# 08_MCU_POWER.net
KiCad netlist of a schematic drawn in Altium Designer
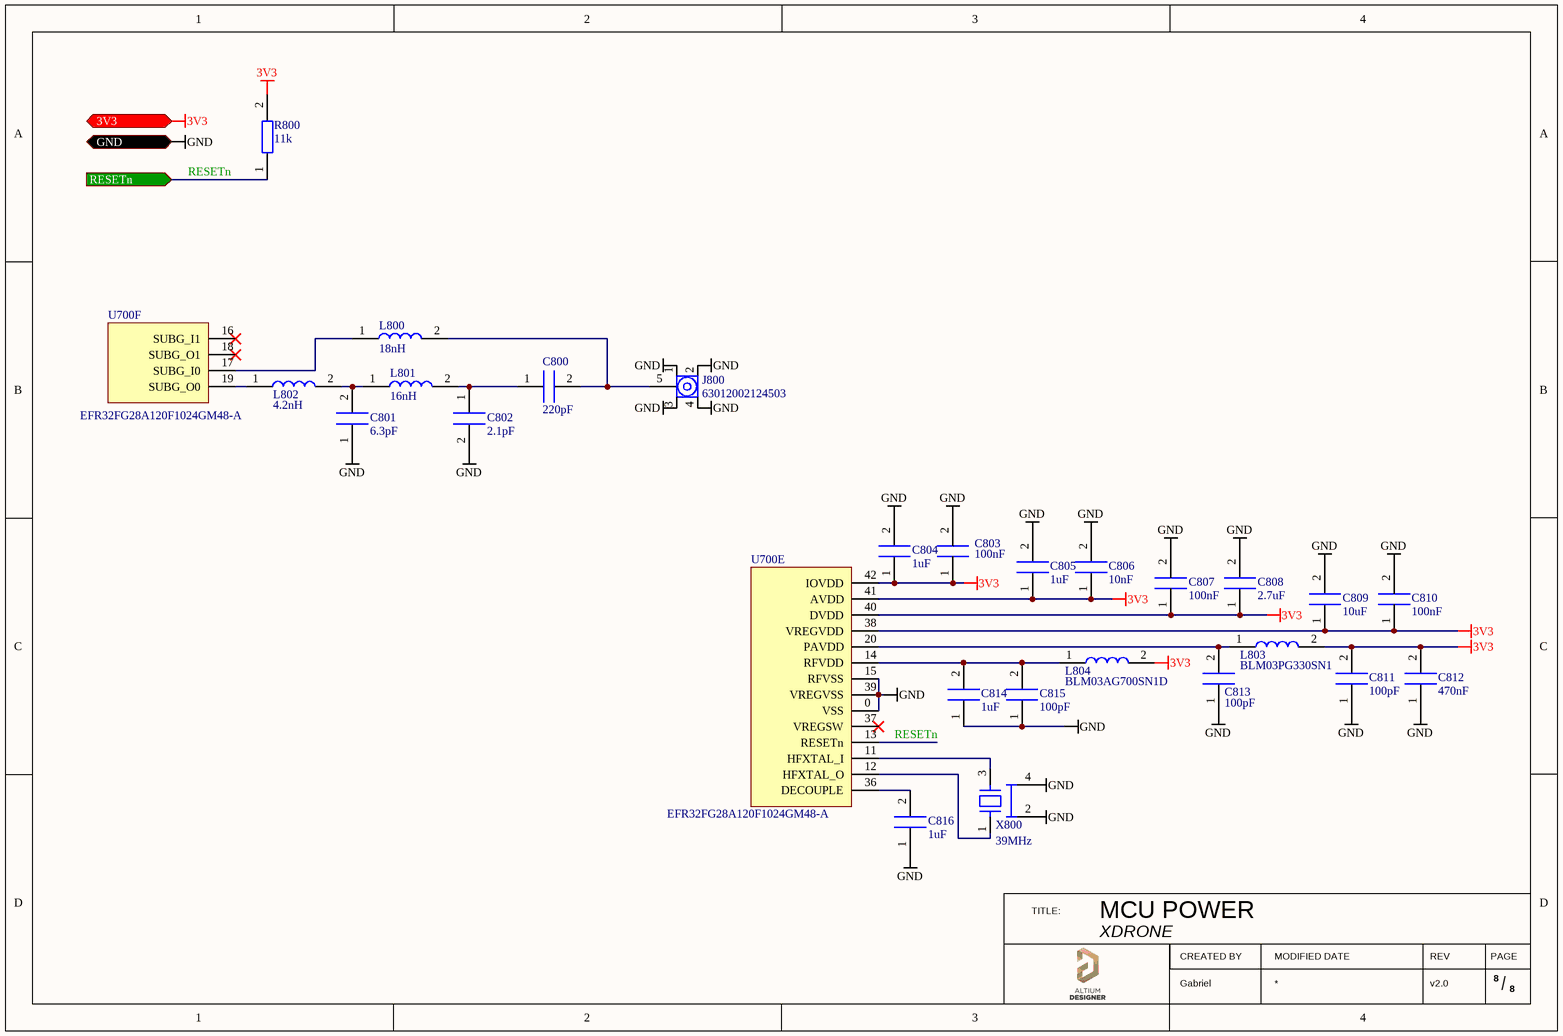
[diagram p0: 08_MCU_POWER.SchDoc]

(export (version "E")
  (design (tool "Eeschema 10.0.6"))
  (components
    (comp (ref "C800")
      (value "220pF")
      (footprint "CAP_0805")
      (description "CAP 220pF 5% 50V 0805 C0G,NP0")
      (fields (field (name "TOLERANCE") "5%") (field (name "MANUFACTURER") "JOHANSON TECHLONOGY"))
      (libsource (lib "Capacitors") (part "220pF_5%_50V_0805_C0G,NP0_QSCT251Q221J1GV001E"))
    )
    (comp (ref "C801")
      (value "6.3pF")
      (footprint "CAP_0402")
      (description "CAPACITOR 6.3pF 1.5% 50V 0402 CBR04C639B5GAC")
      (fields (field (name "TOLERANCE") "1.5%") (field (name "MANUFACTURER") "KEMET"))
      (libsource (lib "Capacitors") (part "6.3pF_1.5%_50V_0402_CBR04C639B5GAC"))
    )
    (comp (ref "C802")
      (value "2.1pF")
      (footprint "CAP_0402")
      (description "CAPACITOR 2.1pF 5% 50V 0402 GJM1555C1H2R1BB01D")
      (fields (field (name "TOLERANCE") "5%") (field (name "MANUFACTURER") "MURATA"))
      (libsource (lib "Capacitors") (part "2.1pF_5%_50V_0402_GJM1555C1H2R1BB01D"))
    )
    (comp (ref "C803")
      (value "100nF")
      (footprint "CAP_0402")
      (description "CAPACITOR 100nF 10% X7R 0402")
      (fields (field (name "TOLERANCE") "10%") (field (name "MANUFACTURER") "MURATA"))
      (libsource (lib "Capacitors") (part "100nF_10%_16V_0402_GRM155R71C104KA88J"))
    )
    (comp (ref "C804")
      (value "1uF")
      (footprint "CAP_0402")
      (description "CAPACITOR 1uF 10% X5R 0402")
      (fields (field (name "TOLERANCE") "10%") (field (name "MANUFACTURER") "MURATA"))
      (libsource (lib "Capacitors") (part "1uF_10%_35V_0402_GRM155R6YA105KE11J"))
    )
    (comp (ref "C805")
      (value "1uF")
      (footprint "CAP_0402")
      (description "CAPACITOR 1uF 10% X5R 0402")
      (fields (field (name "TOLERANCE") "10%") (field (name "MANUFACTURER") "MURATA"))
      (libsource (lib "Capacitors") (part "1uF_10%_35V_0402_GRM155R6YA105KE11J"))
    )
    (comp (ref "C806")
      (value "10nF")
      (footprint "CAP_0402")
      (description "CAPACITOR 10nF 10% 6.3V 0402 CC0402KRX7R5BB103")
      (fields (field (name "TOLERANCE") "10%") (field (name "MANUFACTURER") "YAGEO"))
      (libsource (lib "Capacitors") (part "10nF_10%_6.3V_0402_CC0402KRX7R5BB103"))
    )
    (comp (ref "C807")
      (value "100nF")
      (footprint "CAP_0402")
      (description "CAPACITOR 100nF 10% X7R 0402")
      (fields (field (name "TOLERANCE") "10%") (field (name "MANUFACTURER") "MURATA"))
      (libsource (lib "Capacitors") (part "100nF_10%_16V_0402_GRM155R71C104KA88J"))
    )
    (comp (ref "C808")
      (value "2.7uF")
      (footprint "CAP_0805")
      (description "CAP 2.7uF 10% 10V 0805 X5R C0805C275K8PAC7800")
      (fields (field (name "TOLERANCE") "10%") (field (name "MANUFACTURER") "KEMET"))
      (libsource (lib "Capacitors") (part "2.7uF_10%_10V_0805_X5R_C0805C275K8PAC7800"))
    )
    (comp (ref "C809")
      (value "10uF")
      (footprint "CAP_0402")
      (description "CAPACITOR 10uF 20% 6.3V 0402 GRM155R60J106ME05D")
      (fields (field (name "TOLERANCE") "20%") (field (name "MANUFACTURER") "MURATA"))
      (libsource (lib "Capacitors") (part "10uF 20% 6.3V 0402 GRM155R60J106ME05D"))
    )
    (comp (ref "C810")
      (value "100nF")
      (footprint "CAP_0402")
      (description "CAPACITOR 100nF 10% X7R 0402")
      (fields (field (name "TOLERANCE") "10%") (field (name "MANUFACTURER") "MURATA"))
      (libsource (lib "Capacitors") (part "100nF_10%_16V_0402_GRM155R71C104KA88J"))
    )
    (comp (ref "C811")
      (value "100pF")
      (footprint "CAP_0402")
      (description "CAPACITOR 100pF 5% 50V 0402 CC0402JRNPO9BN101")
      (fields (field (name "TOLERANCE") "5%") (field (name "MANUFACTURER") "YAGEO"))
      (libsource (lib "Capacitors") (part "100pF_5%_50V_0402_CC0402JRNPO9BN101"))
    )
    (comp (ref "C812")
      (value "470nF")
      (footprint "CAP_0402")
      (description "CAPACITOR 470nF 10% 6.3V 0402 GRM155C80J474KE19D")
      (fields (field (name "TOLERANCE") "10%") (field (name "MANUFACTURER") "MURATA"))
      (libsource (lib "Capacitors") (part "470nF_10%_6.3V_0402_GRM155C80J474KE19D"))
    )
    (comp (ref "C813")
      (value "100pF")
      (footprint "CAP_0402")
      (description "CAPACITOR 100pF 5% 50V 0402 CC0402JRNPO9BN101")
      (fields (field (name "TOLERANCE") "5%") (field (name "MANUFACTURER") "YAGEO"))
      (libsource (lib "Capacitors") (part "100pF_5%_50V_0402_CC0402JRNPO9BN101"))
    )
    (comp (ref "C814")
      (value "1uF")
      (footprint "CAP_0402")
      (description "CAPACITOR 1uF 10% X5R 0402")
      (fields (field (name "TOLERANCE") "10%") (field (name "MANUFACTURER") "MURATA"))
      (libsource (lib "Capacitors") (part "1uF_10%_35V_0402_GRM155R6YA105KE11J"))
    )
    (comp (ref "C815")
      (value "100pF")
      (footprint "CAP_0402")
      (description "CAPACITOR 100pF 5% 50V 0402 CC0402JRNPO9BN101")
      (fields (field (name "TOLERANCE") "5%") (field (name "MANUFACTURER") "YAGEO"))
      (libsource (lib "Capacitors") (part "100pF_5%_50V_0402_CC0402JRNPO9BN101"))
    )
    (comp (ref "C816")
      (value "1uF")
      (footprint "CAP_0402")
      (description "CAPACITOR 1uF 10% X5R 0402")
      (fields (field (name "TOLERANCE") "10%") (field (name "MANUFACTURER") "MURATA"))
      (libsource (lib "Capacitors") (part "1uF_10%_35V_0402_GRM155R6YA105KE11J"))
    )
    (comp (ref "J800")
      (value "RF_63012002124503")
      (footprint "RF_63012002124503")
      (description "RF Connector 63012002124503")
      (fields (field (name "MANUFACTURER") "WE") (field (name "MANUFACTURER REFERENCE") "63012002124503"))
      (libsource (lib "Connectors") (part "RF_63012002124503"))
    )
    (comp (ref "L800")
      (value "18nH")
      (footprint "RF_IND_0402")
      (description "INDUCTOR 18nH 2% 400mA LQG15HS18NG02D")
      (fields (field (name "TOLERANCE") "2%") (field (name "MANUFACTURER") "MURATA"))
      (libsource (lib "Inductors") (part "18nH_2%_400mA_LQG15HS18NG02D"))
    )
    (comp (ref "L801")
      (value "16nH")
      (footprint "RF_IND_0402")
      (description "INDUCTOR 16nH 3% 400mA MLG1005S16NHT000")
      (fields (field (name "TOLERANCE") "3%") (field (name "MANUFACTURER") "TDK"))
      (libsource (lib "Inductors") (part "16nH_3%_400mA_MLG1005S16NHT000"))
    )
    (comp (ref "L802")
      (value "4.2nH")
      (footprint "RF_IND_0402")
      (description "INDUCTOR 4.2nH 5% 1.8A LQW15AN4N2C8ZD")
      (fields (field (name "TOLERANCE") "5%") (field (name "MANUFACTURER") "MURATA"))
      (libsource (lib "Inductors") (part "4.2nH_5%_1.8A_LQW15AN4N2C8ZD"))
    )
    (comp (ref "L803")
      (value "52nH_25%_750mA_BLM03PG330SN1")
      (footprint "IND_0201")
      (description "INDUCTOR 52uH 25% 750mA BLM03PG330SN1")
      (fields
        (field (name "TOLERANCE") "25%")
        (field (name "MANUFACTURER") "MURATA")
        (field (name "MANUFACTURER REFERENCE") "BLM03PG330SN1")
      )
      (libsource (lib "Inductors") (part "52nH_25%_750mA_BLM03PG330SN1"))
    )
    (comp (ref "L804")
      (value "110nH_50%_200mA_BLM03AG700SN1D")
      (footprint "IND_0201")
      (description "INDUCTOR 110nH 50% 200mA BLM03AG700SN1D")
      (fields
        (field (name "TOLERANCE") "50%")
        (field (name "MANUFACTURER") "MURATA")
        (field (name "MANUFACTURER REFERENCE") "BLM03AG700SN1D")
      )
      (libsource (lib "Inductors") (part "110nH 50% 200mA BLM03AG700SN1D"))
    )
    (comp (ref "R800")
      (value "11k")
      (footprint "RES_0402")
      (description "RESISTOR 11k 5% 0402 ERJ-2GEJ113X")
      (fields (field (name "TOLERANCE") "5%") (field (name "MANUFACTURER") "PANASONIC"))
      (libsource (lib "Resistors") (part "RES_11k_5%_0402_ERJ-2GEJ113X"))
    )
    (comp (ref "U700")
      (value "MCU_1MB_256kB_EFR32FG28A120F1024GM48-A")
      (footprint "QFN48")
      (description "MCU 1MB 256kB EFR32FG28A120F1024GM48-A")
      (fields
        (field (name "MANUFACTURER") "SILICON LABS")
        (field (name "MANUFACTURER REFERENCE") "EFR32FG28A120F1024GM48-A")
      )
      (libsource (lib "Semiconductor") (part "MCU_1MB_256kB_EFR32FG28A120F1024GM48-A"))
    )
    (comp (ref "X800")
      (value "QUARTZ_39MHz_10ppm_ECS-390-10-37B-CKM-TR")
      (footprint "4-SMD")
      (description "QUARTZ 39MHz 10ppm ECS-390-10-37B-CKM-TR")
      (fields
        (field (name "MANUFACTURER") "ECS")
        (field (name "TOLERANCE") "10 ppm")
        (field (name "FREQUENCY") "39MHz")
      )
      (libsource (lib "Oscillators") (part "QUARTZ_39MHz_10ppm_ECS-390-10-37B-CKM-TR"))
    )
  )
  (nets
    (net (code "1") (name "/RESETn") (class "Default")
      (node (ref "R800") (pin "1") (pinfunction "1_1") (pintype "passive"))
      (node (ref "U700") (pin "13") (pinfunction "RESETn_13") (pintype "passive"))
    )
    (net (code "2") (name "3V3") (class "Default")
      (node (ref "C803") (pin "1") (pinfunction "1_1") (pintype "passive"))
      (node (ref "C804") (pin "1") (pinfunction "1_1") (pintype "passive"))
      (node (ref "C805") (pin "1") (pinfunction "1_1") (pintype "passive"))
      (node (ref "C806") (pin "1") (pinfunction "1_1") (pintype "passive"))
      (node (ref "C807") (pin "1") (pinfunction "1_1") (pintype "passive"))
      (node (ref "C808") (pin "1") (pinfunction "1_1") (pintype "passive"))
      (node (ref "C809") (pin "1") (pinfunction "1_1") (pintype "passive"))
      (node (ref "C810") (pin "1") (pinfunction "1_1") (pintype "passive"))
      (node (ref "C811") (pin "2") (pinfunction "2_2") (pintype "passive"))
      (node (ref "C812") (pin "2") (pinfunction "2_2") (pintype "passive"))
      (node (ref "L803") (pin "2") (pinfunction "2_2") (pintype "passive"))
      (node (ref "L804") (pin "2") (pinfunction "2_2") (pintype "passive"))
      (node (ref "R800") (pin "2") (pinfunction "2_2") (pintype "passive"))
      (node (ref "U700") (pin "38") (pinfunction "VREGVDD_38") (pintype "passive"))
      (node (ref "U700") (pin "40") (pinfunction "DVDD_40") (pintype "passive"))
      (node (ref "U700") (pin "41") (pinfunction "AVDD_41") (pintype "passive"))
      (node (ref "U700") (pin "42") (pinfunction "IOVDD_42") (pintype "passive"))
    )
    (net (code "3") (name "GND") (class "Default")
      (node (ref "C801") (pin "1") (pinfunction "1_1") (pintype "passive"))
      (node (ref "C802") (pin "2") (pinfunction "2_2") (pintype "passive"))
      (node (ref "C803") (pin "2") (pinfunction "2_2") (pintype "passive"))
      (node (ref "C804") (pin "2") (pinfunction "2_2") (pintype "passive"))
      (node (ref "C805") (pin "2") (pinfunction "2_2") (pintype "passive"))
      (node (ref "C806") (pin "2") (pinfunction "2_2") (pintype "passive"))
      (node (ref "C807") (pin "2") (pinfunction "2_2") (pintype "passive"))
      (node (ref "C808") (pin "2") (pinfunction "2_2") (pintype "passive"))
      (node (ref "C809") (pin "2") (pinfunction "2_2") (pintype "passive"))
      (node (ref "C810") (pin "2") (pinfunction "2_2") (pintype "passive"))
      (node (ref "C811") (pin "1") (pinfunction "1_1") (pintype "passive"))
      (node (ref "C812") (pin "1") (pinfunction "1_1") (pintype "passive"))
      (node (ref "C813") (pin "1") (pinfunction "1_1") (pintype "passive"))
      (node (ref "C814") (pin "1") (pinfunction "1_1") (pintype "passive"))
      (node (ref "C815") (pin "1") (pinfunction "1_1") (pintype "passive"))
      (node (ref "C816") (pin "1") (pinfunction "1_1") (pintype "passive"))
      (node (ref "J800") (pin "1") (pinfunction "1_1") (pintype "passive"))
      (node (ref "J800") (pin "2") (pinfunction "2_2") (pintype "passive"))
      (node (ref "J800") (pin "3") (pinfunction "3_3") (pintype "passive"))
      (node (ref "J800") (pin "4") (pinfunction "4_4") (pintype "passive"))
      (node (ref "U700") (pin "0") (pinfunction "VSS_0") (pintype "passive"))
      (node (ref "U700") (pin "15") (pinfunction "RFVSS_15") (pintype "passive"))
      (node (ref "U700") (pin "39") (pinfunction "VREGVSS_39") (pintype "passive"))
      (node (ref "X800") (pin "2") (pinfunction "2_2") (pintype "passive"))
      (node (ref "X800") (pin "4") (pinfunction "4_4") (pintype "passive"))
    )
    (net (code "4") (name "Net-(C800-Pad1)") (class "Default")
      (node (ref "C800") (pin "1") (pinfunction "1_1") (pintype "passive"))
      (node (ref "C802") (pin "1") (pinfunction "1_1") (pintype "passive"))
      (node (ref "L801") (pin "2") (pinfunction "2_2") (pintype "passive"))
    )
    (net (code "5") (name "Net-(C800-Pad2)") (class "Default")
      (node (ref "C800") (pin "2") (pinfunction "2_2") (pintype "passive"))
      (node (ref "J800") (pin "5") (pinfunction "2_5") (pintype "passive"))
      (node (ref "L800") (pin "2") (pinfunction "2_2") (pintype "passive"))
    )
    (net (code "6") (name "Net-(C801-Pad2)") (class "Default")
      (node (ref "C801") (pin "2") (pinfunction "2_2") (pintype "passive"))
      (node (ref "L801") (pin "1") (pinfunction "1_1") (pintype "passive"))
      (node (ref "L802") (pin "2") (pinfunction "2_2") (pintype "passive"))
    )
    (net (code "7") (name "Net-(U700E-DECOUPLE)") (class "Default")
      (node (ref "C816") (pin "2") (pinfunction "2_2") (pintype "passive"))
      (node (ref "U700") (pin "36") (pinfunction "DECOUPLE_36") (pintype "passive"))
    )
    (net (code "8") (name "Net-(U700E-HFXTAL_I)") (class "Default")
      (node (ref "U700") (pin "11") (pinfunction "HFXTAL_I_11") (pintype "passive"))
      (node (ref "X800") (pin "3") (pinfunction "3_3") (pintype "passive"))
    )
    (net (code "9") (name "Net-(U700E-HFXTAL_O)") (class "Default")
      (node (ref "U700") (pin "12") (pinfunction "HFXTAL_O_12") (pintype "passive"))
      (node (ref "X800") (pin "1") (pinfunction "1_1") (pintype "passive"))
    )
    (net (code "10") (name "Net-(U700E-PAVDD)") (class "Default")
      (node (ref "C813") (pin "2") (pinfunction "2_2") (pintype "passive"))
      (node (ref "L803") (pin "1") (pinfunction "1_1") (pintype "passive"))
      (node (ref "U700") (pin "20") (pinfunction "PAVDD_20") (pintype "passive"))
    )
    (net (code "11") (name "Net-(U700E-RFVDD)") (class "Default")
      (node (ref "C814") (pin "2") (pinfunction "2_2") (pintype "passive"))
      (node (ref "C815") (pin "2") (pinfunction "2_2") (pintype "passive"))
      (node (ref "L804") (pin "1") (pinfunction "1_1") (pintype "passive"))
      (node (ref "U700") (pin "14") (pinfunction "RFVDD_14") (pintype "passive"))
    )
    (net (code "12") (name "Net-(U700F-SUBG_I0)") (class "Default")
      (node (ref "L800") (pin "1") (pinfunction "1_1") (pintype "passive"))
      (node (ref "U700") (pin "17") (pinfunction "SUBG_I0_17") (pintype "passive"))
    )
    (net (code "13") (name "Net-(U700F-SUBG_O0)") (class "Default")
      (node (ref "L802") (pin "1") (pinfunction "1_1") (pintype "passive"))
      (node (ref "U700") (pin "19") (pinfunction "SUBG_O0_19") (pintype "passive"))
    )
    (net (code "14") (name "unconnected-(U700E-VREGSW-Pad37)") (class "Default")
      (node (ref "U700") (pin "37") (pinfunction "VREGSW_37") (pintype "passive+no_connect"))
    )
    (net (code "15") (name "unconnected-(U700F-SUBG_I1-Pad16)") (class "Default")
      (node (ref "U700") (pin "16") (pinfunction "SUBG_I1_16") (pintype "passive+no_connect"))
    )
    (net (code "16") (name "unconnected-(U700F-SUBG_O1-Pad18)") (class "Default")
      (node (ref "U700") (pin "18") (pinfunction "SUBG_O1_18") (pintype "passive+no_connect"))
    )
  )
)
